# LED.net
KiCad netlist of a schematic drawn in EAGLE
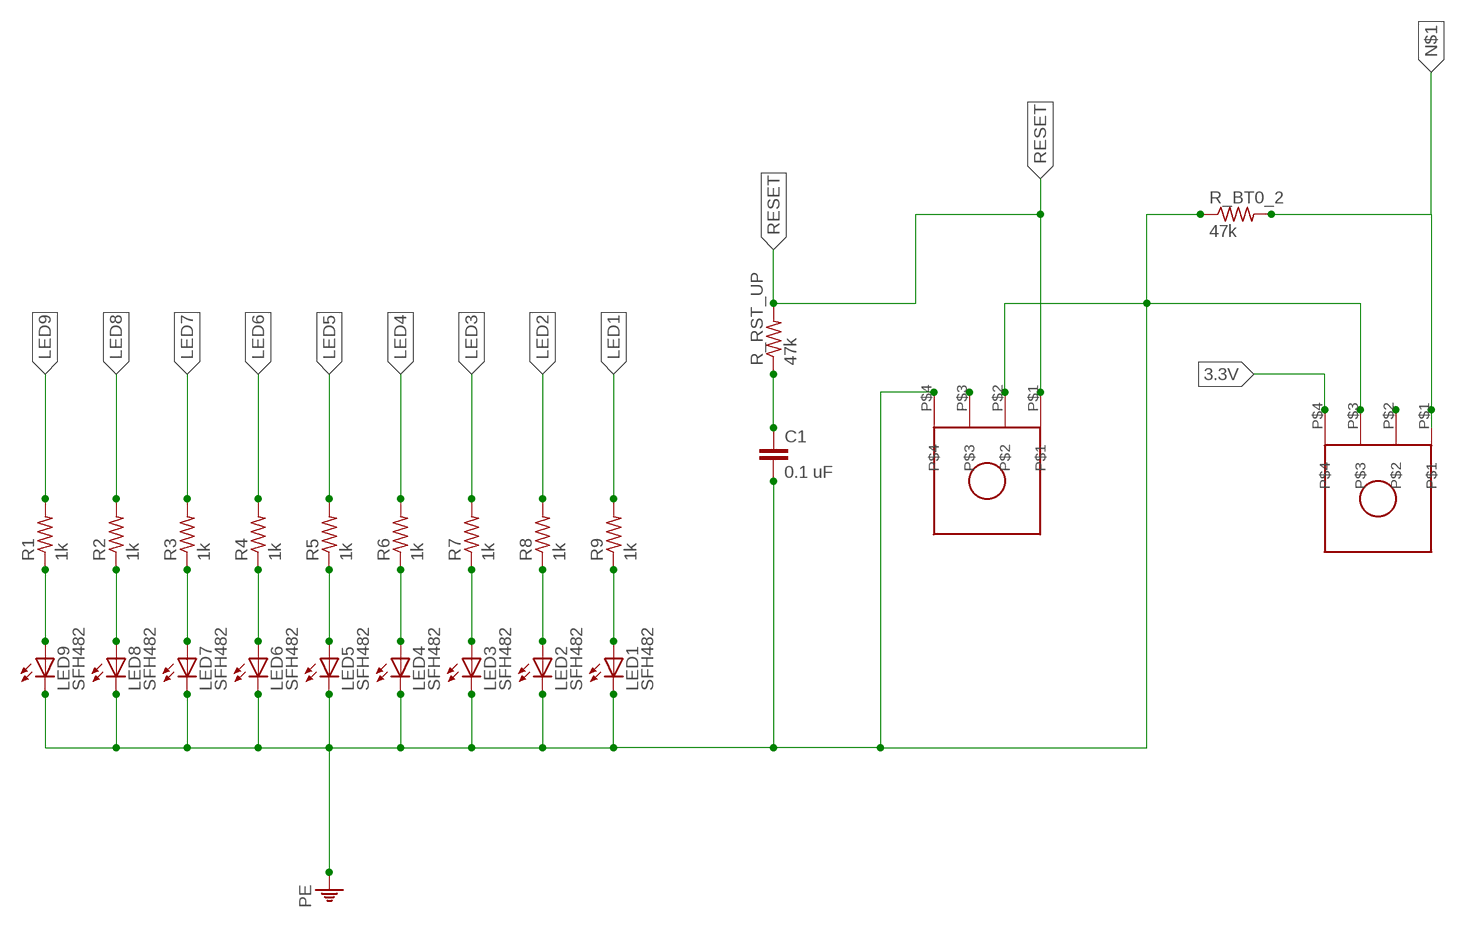
[diagram p0: schematic, sheet 1]

(export (version "E")
  (design (tool "Eeschema 10.0.6"))
  (components
    (comp (ref "1")
      (value "MMBUTTON")
      (footprint "eagle-import:MMBUTTON")
      (libsource (lib "eagle-import") (part "MMBUTTON"))
    )
    (comp (ref "C1")
      (value "0.1 uF")
      (footprint "eagle-import:C0805K")
      (libsource (lib "eagle-import") (part "C-EUC0805K"))
    )
    (comp (ref "LED1")
      (value "SFH482")
      (footprint "eagle-import:SFH482")
      (libsource (lib "eagle-import") (part "SFH482"))
    )
    (comp (ref "LED2")
      (value "SFH482")
      (footprint "eagle-import:SFH482")
      (libsource (lib "eagle-import") (part "SFH482"))
    )
    (comp (ref "LED3")
      (value "SFH482")
      (footprint "eagle-import:SFH482")
      (libsource (lib "eagle-import") (part "SFH482"))
    )
    (comp (ref "LED4")
      (value "SFH482")
      (footprint "eagle-import:SFH482")
      (libsource (lib "eagle-import") (part "SFH482"))
    )
    (comp (ref "LED5")
      (value "SFH482")
      (footprint "eagle-import:SFH482")
      (libsource (lib "eagle-import") (part "SFH482"))
    )
    (comp (ref "LED6")
      (value "SFH482")
      (footprint "eagle-import:SFH482")
      (libsource (lib "eagle-import") (part "SFH482"))
    )
    (comp (ref "LED7")
      (value "SFH482")
      (footprint "eagle-import:SFH482")
      (libsource (lib "eagle-import") (part "SFH482"))
    )
    (comp (ref "LED8")
      (value "SFH482")
      (footprint "eagle-import:SFH482")
      (libsource (lib "eagle-import") (part "SFH482"))
    )
    (comp (ref "LED9")
      (value "SFH482")
      (footprint "eagle-import:SFH482")
      (libsource (lib "eagle-import") (part "SFH482"))
    )
    (comp (ref "R1")
      (value "1k")
      (footprint "eagle-import:R0805W")
      (libsource (lib "eagle-import") (part "R-US_R0805W"))
    )
    (comp (ref "R2")
      (value "1k")
      (footprint "eagle-import:R0805W")
      (libsource (lib "eagle-import") (part "R-US_R0805W"))
    )
    (comp (ref "R3")
      (value "1k")
      (footprint "eagle-import:R0805W")
      (libsource (lib "eagle-import") (part "R-US_R0805W"))
    )
    (comp (ref "R4")
      (value "1k")
      (footprint "eagle-import:R0805W")
      (libsource (lib "eagle-import") (part "R-US_R0805W"))
    )
    (comp (ref "R5")
      (value "1k")
      (footprint "eagle-import:R0805W")
      (libsource (lib "eagle-import") (part "R-US_R0805W"))
    )
    (comp (ref "R6")
      (value "1k")
      (footprint "eagle-import:R0805W")
      (libsource (lib "eagle-import") (part "R-US_R0805W"))
    )
    (comp (ref "R7")
      (value "1k")
      (footprint "eagle-import:R0805W")
      (libsource (lib "eagle-import") (part "R-US_R0805W"))
    )
    (comp (ref "R8")
      (value "1k")
      (footprint "eagle-import:R0805W")
      (libsource (lib "eagle-import") (part "R-US_R0805W"))
    )
    (comp (ref "R9")
      (value "1k")
      (footprint "eagle-import:R0805W")
      (libsource (lib "eagle-import") (part "R-US_R0805W"))
    )
    (comp (ref "R_BT0_2")
      (value "47k")
      (footprint "eagle-import:R1206")
      (libsource (lib "eagle-import") (part "R-US_R1206"))
    )
    (comp (ref "R_RST_UP")
      (value "47k")
      (footprint "eagle-import:R1206")
      (libsource (lib "eagle-import") (part "R-US_R1206"))
    )
    (comp (ref "U$1")
      (value "MMBUTTON")
      (footprint "eagle-import:MMBUTTON")
      (libsource (lib "eagle-import") (part "MMBUTTON"))
    )
  )
  (nets
    (net (code "1") (name "3.3V") (class "Default")
      (node (ref "U$1") (pin "P$4") (pinfunction "P$4_P$4") (pintype "bidirectional"))
    )
    (net (code "2") (name "LED1") (class "Default")
      (node (ref "R9") (pin "2") (pinfunction "2_2") (pintype "passive"))
    )
    (net (code "3") (name "LED2") (class "Default")
      (node (ref "R8") (pin "2") (pinfunction "2_2") (pintype "passive"))
    )
    (net (code "4") (name "LED3") (class "Default")
      (node (ref "R7") (pin "2") (pinfunction "2_2") (pintype "passive"))
    )
    (net (code "5") (name "LED4") (class "Default")
      (node (ref "R6") (pin "2") (pinfunction "2_2") (pintype "passive"))
    )
    (net (code "6") (name "LED5") (class "Default")
      (node (ref "R5") (pin "2") (pinfunction "2_2") (pintype "passive"))
    )
    (net (code "7") (name "LED6") (class "Default")
      (node (ref "R4") (pin "2") (pinfunction "2_2") (pintype "passive"))
    )
    (net (code "8") (name "LED7") (class "Default")
      (node (ref "R3") (pin "2") (pinfunction "2_2") (pintype "passive"))
    )
    (net (code "9") (name "LED8") (class "Default")
      (node (ref "R2") (pin "2") (pinfunction "2_2") (pintype "passive"))
    )
    (net (code "10") (name "LED9") (class "Default")
      (node (ref "R1") (pin "2") (pinfunction "2_2") (pintype "passive"))
    )
    (net (code "11") (name "N$1") (class "Default")
      (node (ref "R_BT0_2") (pin "2") (pinfunction "2_2") (pintype "passive"))
      (node (ref "U$1") (pin "P$1") (pinfunction "P$1_P$1") (pintype "bidirectional"))
    )
    (net (code "12") (name "Net-(C1-Pad1)") (class "Default")
      (node (ref "C1") (pin "1") (pinfunction "1_1") (pintype "passive"))
      (node (ref "R_RST_UP") (pin "1") (pinfunction "1_1") (pintype "passive"))
    )
    (net (code "13") (name "Net-(LED1-PadA)") (class "Default")
      (node (ref "LED1") (pin "A") (pinfunction "A_A") (pintype "passive"))
      (node (ref "R9") (pin "1") (pinfunction "1_1") (pintype "passive"))
    )
    (net (code "14") (name "Net-(LED2-PadA)") (class "Default")
      (node (ref "LED2") (pin "A") (pinfunction "A_A") (pintype "passive"))
      (node (ref "R8") (pin "1") (pinfunction "1_1") (pintype "passive"))
    )
    (net (code "15") (name "Net-(LED3-PadA)") (class "Default")
      (node (ref "LED3") (pin "A") (pinfunction "A_A") (pintype "passive"))
      (node (ref "R7") (pin "1") (pinfunction "1_1") (pintype "passive"))
    )
    (net (code "16") (name "Net-(LED4-PadA)") (class "Default")
      (node (ref "LED4") (pin "A") (pinfunction "A_A") (pintype "passive"))
      (node (ref "R6") (pin "1") (pinfunction "1_1") (pintype "passive"))
    )
    (net (code "17") (name "Net-(LED5-PadA)") (class "Default")
      (node (ref "LED5") (pin "A") (pinfunction "A_A") (pintype "passive"))
      (node (ref "R5") (pin "1") (pinfunction "1_1") (pintype "passive"))
    )
    (net (code "18") (name "Net-(LED6-PadA)") (class "Default")
      (node (ref "LED6") (pin "A") (pinfunction "A_A") (pintype "passive"))
      (node (ref "R4") (pin "1") (pinfunction "1_1") (pintype "passive"))
    )
    (net (code "19") (name "Net-(LED7-PadA)") (class "Default")
      (node (ref "LED7") (pin "A") (pinfunction "A_A") (pintype "passive"))
      (node (ref "R3") (pin "1") (pinfunction "1_1") (pintype "passive"))
    )
    (net (code "20") (name "Net-(LED8-PadA)") (class "Default")
      (node (ref "LED8") (pin "A") (pinfunction "A_A") (pintype "passive"))
      (node (ref "R2") (pin "1") (pinfunction "1_1") (pintype "passive"))
    )
    (net (code "21") (name "Net-(LED9-PadA)") (class "Default")
      (node (ref "LED9") (pin "A") (pinfunction "A_A") (pintype "passive"))
      (node (ref "R1") (pin "1") (pinfunction "1_1") (pintype "passive"))
    )
    (net (code "22") (name "PE") (class "Default")
      (node (ref "1") (pin "P$2") (pinfunction "P$2_P$2") (pintype "bidirectional"))
      (node (ref "1") (pin "P$4") (pinfunction "P$4_P$4") (pintype "bidirectional"))
      (node (ref "C1") (pin "2") (pinfunction "2_2") (pintype "passive"))
      (node (ref "LED1") (pin "K") (pinfunction "C_K") (pintype "passive"))
      (node (ref "LED2") (pin "K") (pinfunction "C_K") (pintype "passive"))
      (node (ref "LED3") (pin "K") (pinfunction "C_K") (pintype "passive"))
      (node (ref "LED4") (pin "K") (pinfunction "C_K") (pintype "passive"))
      (node (ref "LED5") (pin "K") (pinfunction "C_K") (pintype "passive"))
      (node (ref "LED6") (pin "K") (pinfunction "C_K") (pintype "passive"))
      (node (ref "LED7") (pin "K") (pinfunction "C_K") (pintype "passive"))
      (node (ref "LED8") (pin "K") (pinfunction "C_K") (pintype "passive"))
      (node (ref "LED9") (pin "K") (pinfunction "C_K") (pintype "passive"))
      (node (ref "R_BT0_2") (pin "1") (pinfunction "1_1") (pintype "passive"))
      (node (ref "U$1") (pin "P$3") (pinfunction "P$3_P$3") (pintype "bidirectional"))
    )
    (net (code "23") (name "RESET") (class "Default")
      (node (ref "1") (pin "P$1") (pinfunction "P$1_P$1") (pintype "bidirectional"))
      (node (ref "R_RST_UP") (pin "2") (pinfunction "2_2") (pintype "passive"))
    )
    (net (code "24") (name "unconnected-(1-PadP$3)") (class "Default")
      (node (ref "1") (pin "P$3") (pinfunction "P$3_P$3") (pintype "bidirectional"))
    )
    (net (code "25") (name "unconnected-(U$1-PadP$2)") (class "Default")
      (node (ref "U$1") (pin "P$2") (pinfunction "P$2_P$2") (pintype "bidirectional"))
    )
  )
)
